# ChatBOT.net
KiCad netlist of a schematic drawn in EasyEDA Pro
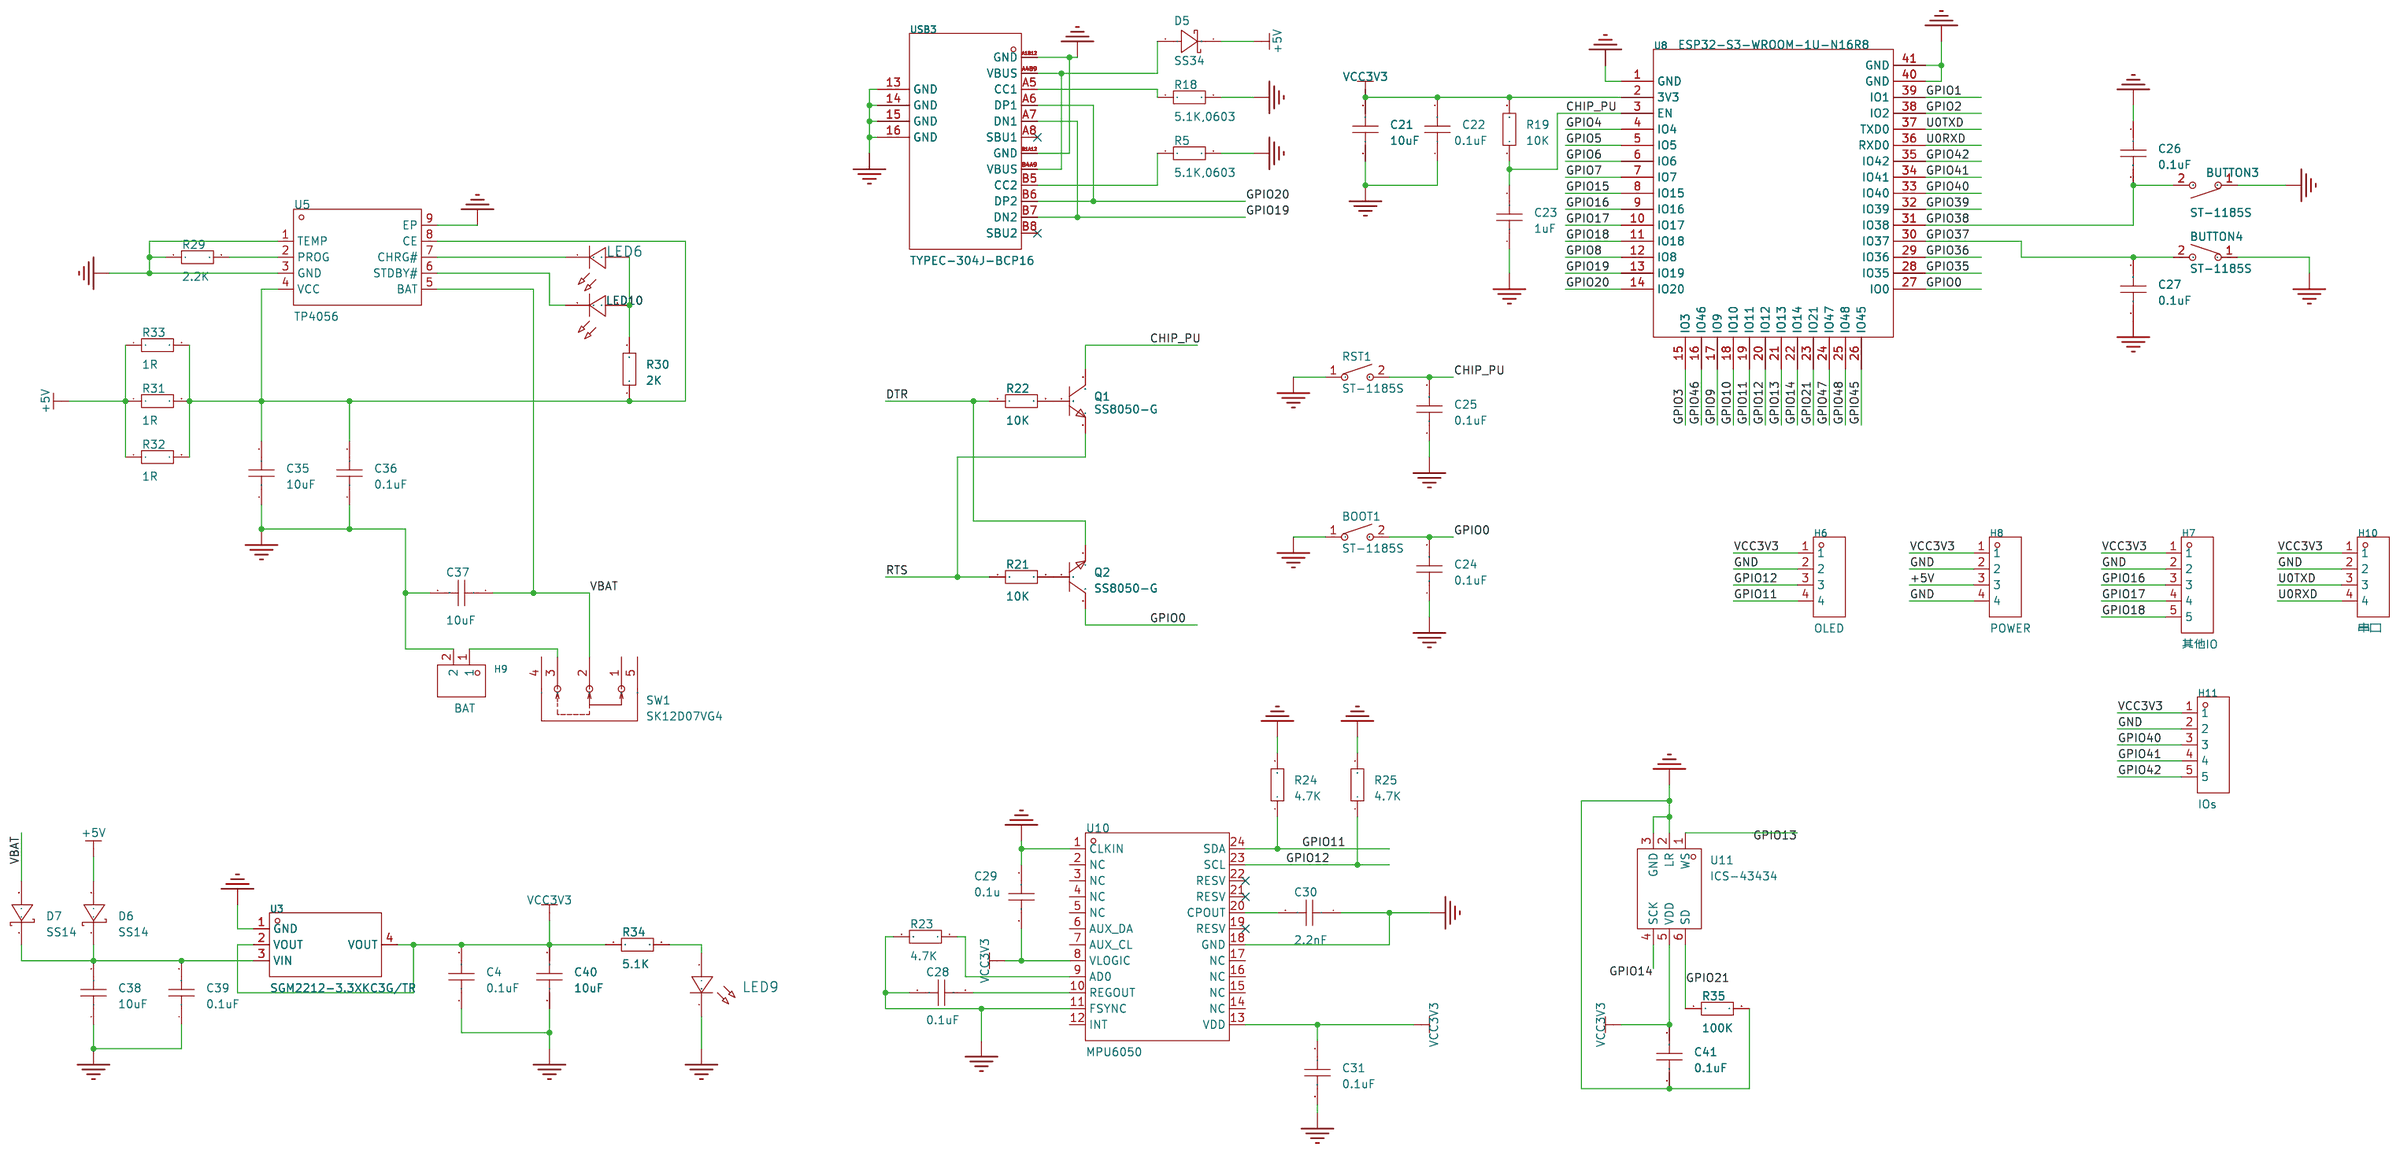
[diagram p0: schematic sheet]

(export (version "E")
  (design (tool "Eeschema 10.0.6"))
  (components
    (comp (ref "BOOT1")
      (value "ST-1185S")
      (footprint "easyedapro:SW-SMD_ST-1185S")
      (description "触点电流:50mA;额定电压(DC):12V;绝缘电阻:100MΩ;电路结构:单刀单掷;安装方式:立贴;机械寿命:10万次;带支架:否;")
      (fields (field (name "Manufacturer") "RISHENG(日昇)"))
      (libsource (lib "easyedapro") (part "ST-1185S"))
    )
    (comp (ref "BUTTON3")
      (value "ST-1185S")
      (footprint "easyedapro:SW-SMD_ST-1185S")
      (description "触点电流:50mA;额定电压(DC):12V;绝缘电阻:100MΩ;电路结构:单刀单掷;安装方式:立贴;机械寿命:10万次;带支架:否;")
      (fields (field (name "Manufacturer") "RISHENG(日昇)"))
      (libsource (lib "easyedapro") (part "ST-1185S"))
    )
    (comp (ref "BUTTON4")
      (value "ST-1185S")
      (footprint "easyedapro:SW-SMD_ST-1185S")
      (description "触点电流:50mA;额定电压(DC):12V;绝缘电阻:100MΩ;电路结构:单刀单掷;安装方式:立贴;机械寿命:10万次;带支架:否;")
      (fields (field (name "Manufacturer") "RISHENG(日昇)"))
      (libsource (lib "easyedapro") (part "ST-1185S"))
    )
    (comp (ref "C4")
      (value "0.1uF")
      (footprint "easyedapro:C0603")
      (libsource (lib "easyedapro") (part "CapAcitance"))
    )
    (comp (ref "C21")
      (value "10uF")
      (footprint "easyedapro:C0603")
      (libsource (lib "easyedapro") (part "CapAcitance"))
    )
    (comp (ref "C22")
      (value "0.1uF")
      (footprint "easyedapro:C0603")
      (libsource (lib "easyedapro") (part "CapAcitance"))
    )
    (comp (ref "C23")
      (value "1uF")
      (footprint "easyedapro:C0603")
      (libsource (lib "easyedapro") (part "CapAcitance"))
    )
    (comp (ref "C24")
      (value "0.1uF")
      (footprint "easyedapro:C0603")
      (libsource (lib "easyedapro") (part "CapAcitance"))
    )
    (comp (ref "C25")
      (value "0.1uF")
      (footprint "easyedapro:C0603")
      (libsource (lib "easyedapro") (part "CapAcitance"))
    )
    (comp (ref "C26")
      (value "0.1uF")
      (footprint "easyedapro:C0603")
      (libsource (lib "easyedapro") (part "CapAcitance"))
    )
    (comp (ref "C27")
      (value "0.1uF")
      (footprint "easyedapro:C0603")
      (libsource (lib "easyedapro") (part "CapAcitance"))
    )
    (comp (ref "C28")
      (value "0.1uF")
      (footprint "easyedapro:C0603")
      (libsource (lib "easyedapro") (part "CapAcitance"))
    )
    (comp (ref "C29")
      (value "0.1u")
      (footprint "easyedapro:C0603")
      (libsource (lib "easyedapro") (part "CapAcitance"))
    )
    (comp (ref "C30")
      (value "2.2nF")
      (footprint "easyedapro:C0603")
      (libsource (lib "easyedapro") (part "CapAcitance"))
    )
    (comp (ref "C31")
      (value "0.1uF")
      (footprint "easyedapro:C0603")
      (libsource (lib "easyedapro") (part "CapAcitance"))
    )
    (comp (ref "C35")
      (value "10uF")
      (footprint "easyedapro:C0603")
      (libsource (lib "easyedapro") (part "CapAcitance"))
    )
    (comp (ref "C36")
      (value "0.1uF")
      (footprint "easyedapro:C0603")
      (libsource (lib "easyedapro") (part "CapAcitance"))
    )
    (comp (ref "C37")
      (value "10uF")
      (footprint "easyedapro:C0603")
      (libsource (lib "easyedapro") (part "CapAcitance"))
    )
    (comp (ref "C38")
      (value "10uF")
      (footprint "easyedapro:C0603")
      (libsource (lib "easyedapro") (part "CapAcitance"))
    )
    (comp (ref "C39")
      (value "0.1uF")
      (footprint "easyedapro:C0603")
      (libsource (lib "easyedapro") (part "CapAcitance"))
    )
    (comp (ref "C40")
      (value "10uF")
      (footprint "easyedapro:C0603")
      (libsource (lib "easyedapro") (part "CapAcitance"))
    )
    (comp (ref "C41")
      (value "0.1uF")
      (footprint "easyedapro:C0603")
      (libsource (lib "easyedapro") (part "CapAcitance"))
    )
    (comp (ref "D5")
      (value "SS34")
      (footprint "easyedapro:SMA_L4.3-W2.5-LS5.0-RD")
      (description "二极管配置:独立式;直流反向耐压(Vr):40V;平均整流电流(Io):3A;正向压降(Vf):550mV@3A;")
      (fields (field (name "Manufacturer") "TWGMC(台湾迪嘉)"))
      (libsource (lib "easyedapro") (part "SS34_C727060"))
    )
    (comp (ref "D6")
      (value "SS14")
      (footprint "easyedapro:SMA_L4.2-W2.6-LS5.3-RD")
      (description "二极管配置:独立式;正向压降(Vf):550mV@1A;直流反向耐压(Vr):40V;平均整流电流(Io):1A;")
      (fields (field (name "Manufacturer") "MDD"))
      (libsource (lib "easyedapro") (part "SS14"))
    )
    (comp (ref "D7")
      (value "SS14")
      (footprint "easyedapro:SMA_L4.2-W2.6-LS5.3-RD")
      (description "二极管配置:独立式;正向压降(Vf):550mV@1A;直流反向耐压(Vr):40V;平均整流电流(Io):1A;")
      (fields (field (name "Manufacturer") "MDD"))
      (libsource (lib "easyedapro") (part "SS14"))
    )
    (comp (ref "H6")
      (value "OLED")
      (footprint "easyedapro:HDR-TH_4P-P2.54-V-M")
      (fields (field (name "Manufacturer") "XFCN(兴飞)"))
      (libsource (lib "easyedapro") (part "PZ254V-11-04P_C2691448"))
    )
    (comp (ref "H7")
      (value "其他IO")
      (footprint "easyedapro:HDR-TH_5P-P2.54-V-M")
      (fields (field (name "Manufacturer") "XFCN(兴飞)"))
      (libsource (lib "easyedapro") (part "PZ254V-11-05P"))
    )
    (comp (ref "H8")
      (value "POWER")
      (footprint "easyedapro:HDR-TH_4P-P2.54-V-M")
      (fields (field (name "Manufacturer") "XFCN(兴飞)"))
      (libsource (lib "easyedapro") (part "PZ254V-11-04P_C2691448"))
    )
    (comp (ref "H9")
      (value "BAT")
      (footprint "easyedapro:HDR-TH_2P-P2.54-V-M")
      (fields (field (name "Manufacturer") "XFCN(兴飞)"))
      (libsource (lib "easyedapro") (part "PZ254V-11-02P"))
    )
    (comp (ref "H10")
      (value "串口")
      (footprint "easyedapro:HDR-TH_4P-P2.54-V-M")
      (fields (field (name "Manufacturer") "XFCN(兴飞)"))
      (libsource (lib "easyedapro") (part "PZ254V-11-04P_C2691448"))
    )
    (comp (ref "H11")
      (value "IOs")
      (footprint "easyedapro:HDR-TH_5P-P2.54-V-M")
      (fields (field (name "Manufacturer") "XFCN(兴飞)"))
      (libsource (lib "easyedapro") (part "PZ254V-11-05P"))
    )
    (comp (ref "LED6")
      (value "~")
      (footprint "easyedapro:LED_0603")
      (libsource (lib "easyedapro") (part "LED_R"))
    )
    (comp (ref "LED9")
      (value "~")
      (footprint "easyedapro:LED_0603")
      (libsource (lib "easyedapro") (part "LED_R"))
    )
    (comp (ref "LED10")
      (value "~")
      (footprint "easyedapro:LED_0603")
      (libsource (lib "easyedapro") (part "LED_G"))
    )
    (comp (ref "Q1")
      (value "SS8050-G")
      (footprint "easyedapro:SOT-23-3_L2.9-W1.6-P1.90-LS2.8-BR")
      (description "晶体管类型:NPN;集射极击穿电压(Vceo):25V;集电极电流(Ic):1.5A;功率(Pd):300mW;直流电流增益(hFE@Ic,Vce):120@100mA,1V;")
      (fields (field (name "Manufacturer") "CJ(江苏长电/长晶)"))
      (libsource (lib "easyedapro") (part "SS8050-G"))
    )
    (comp (ref "Q2")
      (value "SS8050-G")
      (footprint "easyedapro:SOT-23-3_L2.9-W1.6-P1.90-LS2.8-BR")
      (description "晶体管类型:NPN;集射极击穿电压(Vceo):25V;集电极电流(Ic):1.5A;功率(Pd):300mW;直流电流增益(hFE@Ic,Vce):120@100mA,1V;")
      (fields (field (name "Manufacturer") "CJ(江苏长电/长晶)"))
      (libsource (lib "easyedapro") (part "SS8050-G"))
    )
    (comp (ref "R5")
      (value "5.1K,0603")
      (footprint "easyedapro:R0603")
      (libsource (lib "easyedapro") (part "电阻"))
    )
    (comp (ref "R18")
      (value "5.1K,0603")
      (footprint "easyedapro:R0603")
      (libsource (lib "easyedapro") (part "电阻"))
    )
    (comp (ref "R19") (value "10K") (footprint "easyedapro:R0603") (libsource (lib "easyedapro") (part "电阻")))
    (comp (ref "R21") (value "10K") (footprint "easyedapro:R0603") (libsource (lib "easyedapro") (part "电阻")))
    (comp (ref "R22") (value "10K") (footprint "easyedapro:R0603") (libsource (lib "easyedapro") (part "电阻")))
    (comp (ref "R23")
      (value "4.7K")
      (footprint "easyedapro:R0603")
      (libsource (lib "easyedapro") (part "电阻"))
    )
    (comp (ref "R24")
      (value "4.7K")
      (footprint "easyedapro:R0603")
      (libsource (lib "easyedapro") (part "电阻"))
    )
    (comp (ref "R25")
      (value "4.7K")
      (footprint "easyedapro:R0603")
      (libsource (lib "easyedapro") (part "电阻"))
    )
    (comp (ref "R29")
      (value "2.2K")
      (footprint "easyedapro:R0603")
      (libsource (lib "easyedapro") (part "电阻"))
    )
    (comp (ref "R30") (value "2K") (footprint "easyedapro:R0603") (libsource (lib "easyedapro") (part "电阻")))
    (comp (ref "R31") (value "1R") (footprint "easyedapro:R0603") (libsource (lib "easyedapro") (part "电阻")))
    (comp (ref "R32") (value "1R") (footprint "easyedapro:R0603") (libsource (lib "easyedapro") (part "电阻")))
    (comp (ref "R33") (value "1R") (footprint "easyedapro:R0603") (libsource (lib "easyedapro") (part "电阻")))
    (comp (ref "R34")
      (value "5.1K")
      (footprint "easyedapro:R0603")
      (libsource (lib "easyedapro") (part "电阻"))
    )
    (comp (ref "R35")
      (value "100K")
      (footprint "easyedapro:R0603")
      (libsource (lib "easyedapro") (part "电阻"))
    )
    (comp (ref "RST1")
      (value "ST-1185S")
      (footprint "easyedapro:SW-SMD_ST-1185S")
      (description "触点电流:50mA;额定电压(DC):12V;绝缘电阻:100MΩ;电路结构:单刀单掷;安装方式:立贴;机械寿命:10万次;带支架:否;")
      (fields (field (name "Manufacturer") "RISHENG(日昇)"))
      (libsource (lib "easyedapro") (part "ST-1185S"))
    )
    (comp (ref "SW1")
      (value "SK12D07VG4")
      (footprint "easyedapro:SW-TH_SK12D07VG4")
      (description "电路结构:单刀双掷;安装方式:卧插;额定电流(DC):500mA;额定电压(DC):50V;额定电流(AC):-;额定电压(AC):-;机械寿命:5千次;")
      (fields (field (name "Manufacturer") "SHOU HAN(首韩)"))
      (libsource (lib "easyedapro") (part "SK12D07VG4"))
    )
    (comp (ref "U3")
      (value "SGM2212-3.3XKC3G/TR")
      (footprint "easyedapro:SOT-223-3_L6.5-W3.4-P2.30-LS7.0-BR")
      (fields (field (name "Manufacturer") "SGMICRO(圣邦微)"))
      (libsource (lib "easyedapro") (part "SGM2212-3.3XKC3G/TR_C3294699"))
    )
    (comp (ref "U5")
      (value "TP4056")
      (footprint "easyedapro:ESOP-8_L4.9-W3.9-P1.27-LS6.0-BL-EP")
      (fields (field (name "Manufacturer") "UMW(友台半导体)"))
      (libsource (lib "easyedapro") (part "TP4056_C725790"))
    )
    (comp (ref "U8")
      (value "ESP32-S3-WROOM-1U-N16R8")
      (footprint "easyedapro:WIRELM-SMD_ESP32-S3-WROOM-1U")
      (fields (field (name "Manufacturer") "ESPRESSIF(乐鑫)"))
      (libsource (lib "easyedapro") (part "ESP32-S3-WROOM-1U-N16R8"))
    )
    (comp (ref "U10")
      (value "MPU6050")
      (footprint "easyedapro:QFN-24_L4.0-W4.0-P0.50-BL")
      (libsource (lib "easyedapro") (part "MPU6050_C9900042518"))
    )
    (comp (ref "U11")
      (value "ICS-43434")
      (footprint "easyedapro:MIC-SMD_6P-L3.5-W2.7-P0.90-TR")
      (description "方向:全指向;信噪比:64dB;灵敏度:-;")
      (fields (field (name "Manufacturer") "TDK InvenSense(应美盛)"))
      (libsource (lib "easyedapro") (part "ICS-43434_C5656610"))
    )
    (comp (ref "USB3")
      (value "TYPEC-304J-BCP16")
      (footprint "easyedapro:USB-C-SMD_TYPEC-304J-BCP16")
      (description "连接器类型:Type-C;标准:USB 3.1;公母:母座;触点数量:16;端口数量:1;安装方式:卧贴;额定电流 - 电源:5A;工作温度范围:-40℃~+85℃;焊接温度(最大值):260℃;")
      (fields (field (name "Manufacturer") "XUNPU(讯普)"))
      (libsource (lib "easyedapro") (part "TYPEC-304J-BCP16"))
    )
  )
  (nets
    (net (code "1") (name "+5V") (class "Default")
      (node (ref "D5") (pin "1") (pinfunction "C_1") (pintype "unspecified"))
      (node (ref "D6") (pin "2") (pinfunction "A_2") (pintype "unspecified"))
      (node (ref "H8") (pin "3") (pinfunction "3_3") (pintype "input"))
      (node (ref "R31") (pin "1") (pinfunction "1_1") (pintype "input"))
      (node (ref "R32") (pin "1") (pinfunction "1_1") (pintype "input"))
      (node (ref "R33") (pin "1") (pinfunction "1_1") (pintype "input"))
    )
    (net (code "2") (name "/CHIP_PU") (class "Default")
      (node (ref "C23") (pin "2") (pinfunction "2_2") (pintype "input"))
      (node (ref "C25") (pin "2") (pinfunction "2_2") (pintype "input"))
      (node (ref "Q1") (pin "3") (pinfunction "C_3") (pintype "input"))
      (node (ref "R19") (pin "1") (pinfunction "1_1") (pintype "input"))
      (node (ref "RST1") (pin "2") (pinfunction "2_2") (pintype "unspecified"))
      (node (ref "U8") (pin "3") (pinfunction "EN_3") (pintype "unspecified"))
    )
    (net (code "3") (name "/DTR") (class "Default")
      (node (ref "Q2") (pin "2") (pinfunction "E_2") (pintype "input"))
      (node (ref "R22") (pin "1") (pinfunction "1_1") (pintype "input"))
    )
    (net (code "4") (name "/GPIO0") (class "Default")
      (node (ref "BOOT1") (pin "2") (pinfunction "2_2") (pintype "unspecified"))
      (node (ref "C24") (pin "2") (pinfunction "2_2") (pintype "input"))
      (node (ref "Q2") (pin "3") (pinfunction "C_3") (pintype "input"))
      (node (ref "U8") (pin "27") (pinfunction "IO0_27") (pintype "unspecified"))
    )
    (net (code "5") (name "/GPIO1") (class "Default")
      (node (ref "U8") (pin "39") (pinfunction "IO1_39") (pintype "unspecified"))
    )
    (net (code "6") (name "/GPIO2") (class "Default")
      (node (ref "U8") (pin "38") (pinfunction "IO2_38") (pintype "unspecified"))
    )
    (net (code "7") (name "/GPIO3") (class "Default")
      (node (ref "U8") (pin "15") (pinfunction "IO3_15") (pintype "unspecified"))
    )
    (net (code "8") (name "/GPIO4") (class "Default")
      (node (ref "U8") (pin "4") (pinfunction "IO4_4") (pintype "unspecified"))
    )
    (net (code "9") (name "/GPIO5") (class "Default")
      (node (ref "U8") (pin "5") (pinfunction "IO5_5") (pintype "unspecified"))
    )
    (net (code "10") (name "/GPIO6") (class "Default")
      (node (ref "U8") (pin "6") (pinfunction "IO6_6") (pintype "unspecified"))
    )
    (net (code "11") (name "/GPIO7") (class "Default")
      (node (ref "U8") (pin "7") (pinfunction "IO7_7") (pintype "unspecified"))
    )
    (net (code "12") (name "/GPIO8") (class "Default")
      (node (ref "U8") (pin "12") (pinfunction "IO8_12") (pintype "unspecified"))
    )
    (net (code "13") (name "/GPIO9") (class "Default")
      (node (ref "U8") (pin "17") (pinfunction "IO9_17") (pintype "unspecified"))
    )
    (net (code "14") (name "/GPIO10") (class "Default")
      (node (ref "U8") (pin "18") (pinfunction "IO10_18") (pintype "unspecified"))
    )
    (net (code "15") (name "/GPIO11") (class "Default")
      (node (ref "H6") (pin "4") (pinfunction "4_4") (pintype "input"))
      (node (ref "R24") (pin "1") (pinfunction "1_1") (pintype "input"))
      (node (ref "U10") (pin "24") (pinfunction "SDA_24") (pintype "unspecified"))
      (node (ref "U8") (pin "19") (pinfunction "IO11_19") (pintype "unspecified"))
    )
    (net (code "16") (name "/GPIO12") (class "Default")
      (node (ref "H6") (pin "3") (pinfunction "3_3") (pintype "input"))
      (node (ref "R25") (pin "1") (pinfunction "1_1") (pintype "input"))
      (node (ref "U10") (pin "23") (pinfunction "SCL_23") (pintype "unspecified"))
      (node (ref "U8") (pin "20") (pinfunction "IO12_20") (pintype "unspecified"))
    )
    (net (code "17") (name "/GPIO13") (class "Default")
      (node (ref "U11") (pin "1") (pinfunction "WS_1") (pintype "unspecified"))
      (node (ref "U8") (pin "21") (pinfunction "IO13_21") (pintype "unspecified"))
    )
    (net (code "18") (name "/GPIO14") (class "Default")
      (node (ref "U11") (pin "4") (pinfunction "SCK_4") (pintype "unspecified"))
      (node (ref "U8") (pin "22") (pinfunction "IO14_22") (pintype "unspecified"))
    )
    (net (code "19") (name "/GPIO15") (class "Default")
      (node (ref "U8") (pin "8") (pinfunction "IO15_8") (pintype "unspecified"))
    )
    (net (code "20") (name "/GPIO16") (class "Default")
      (node (ref "H7") (pin "3") (pinfunction "3_3") (pintype "unspecified"))
      (node (ref "U8") (pin "9") (pinfunction "IO16_9") (pintype "unspecified"))
    )
    (net (code "21") (name "/GPIO17") (class "Default")
      (node (ref "H7") (pin "4") (pinfunction "4_4") (pintype "unspecified"))
      (node (ref "U8") (pin "10") (pinfunction "IO17_10") (pintype "unspecified"))
    )
    (net (code "22") (name "/GPIO18") (class "Default")
      (node (ref "H7") (pin "5") (pinfunction "5_5") (pintype "unspecified"))
      (node (ref "U8") (pin "11") (pinfunction "IO18_11") (pintype "unspecified"))
    )
    (net (code "23") (name "/GPIO19") (class "Default")
      (node (ref "U8") (pin "13") (pinfunction "IO19_13") (pintype "unspecified"))
      (node (ref "USB3") (pin "A7") (pinfunction "DN1_A7") (pintype "unspecified"))
      (node (ref "USB3") (pin "B7") (pinfunction "DN2_B7") (pintype "unspecified"))
    )
    (net (code "24") (name "/GPIO20") (class "Default")
      (node (ref "U8") (pin "14") (pinfunction "IO20_14") (pintype "unspecified"))
      (node (ref "USB3") (pin "A6") (pinfunction "DP1_A6") (pintype "unspecified"))
      (node (ref "USB3") (pin "B6") (pinfunction "DP2_B6") (pintype "unspecified"))
    )
    (net (code "25") (name "/GPIO21") (class "Default")
      (node (ref "R35") (pin "1") (pinfunction "1_1") (pintype "input"))
      (node (ref "U11") (pin "6") (pinfunction "SD_6") (pintype "unspecified"))
      (node (ref "U8") (pin "23") (pinfunction "IO21_23") (pintype "unspecified"))
    )
    (net (code "26") (name "/GPIO35") (class "Default")
      (node (ref "U8") (pin "28") (pinfunction "IO35_28") (pintype "unspecified"))
    )
    (net (code "27") (name "/GPIO36") (class "Default")
      (node (ref "U8") (pin "29") (pinfunction "IO36_29") (pintype "unspecified"))
    )
    (net (code "28") (name "/GPIO37") (class "Default")
      (node (ref "BUTTON4") (pin "2") (pinfunction "2_2") (pintype "unspecified"))
      (node (ref "C27") (pin "2") (pinfunction "2_2") (pintype "input"))
      (node (ref "U8") (pin "30") (pinfunction "IO37_30") (pintype "unspecified"))
    )
    (net (code "29") (name "/GPIO38") (class "Default")
      (node (ref "BUTTON3") (pin "2") (pinfunction "2_2") (pintype "unspecified"))
      (node (ref "C26") (pin "2") (pinfunction "2_2") (pintype "input"))
      (node (ref "U8") (pin "31") (pinfunction "IO38_31") (pintype "unspecified"))
    )
    (net (code "30") (name "/GPIO39") (class "Default")
      (node (ref "U8") (pin "32") (pinfunction "IO39_32") (pintype "unspecified"))
    )
    (net (code "31") (name "/GPIO40") (class "Default")
      (node (ref "H11") (pin "3") (pinfunction "3_3") (pintype "unspecified"))
      (node (ref "U8") (pin "33") (pinfunction "IO40_33") (pintype "unspecified"))
    )
    (net (code "32") (name "/GPIO41") (class "Default")
      (node (ref "H11") (pin "4") (pinfunction "4_4") (pintype "unspecified"))
      (node (ref "U8") (pin "34") (pinfunction "IO41_34") (pintype "unspecified"))
    )
    (net (code "33") (name "/GPIO42") (class "Default")
      (node (ref "H11") (pin "5") (pinfunction "5_5") (pintype "unspecified"))
      (node (ref "U8") (pin "35") (pinfunction "IO42_35") (pintype "unspecified"))
    )
    (net (code "34") (name "/GPIO45") (class "Default")
      (node (ref "U8") (pin "26") (pinfunction "IO45_26") (pintype "unspecified"))
    )
    (net (code "35") (name "/GPIO46") (class "Default")
      (node (ref "U8") (pin "16") (pinfunction "IO46_16") (pintype "unspecified"))
    )
    (net (code "36") (name "/GPIO47") (class "Default")
      (node (ref "U8") (pin "24") (pinfunction "IO47_24") (pintype "unspecified"))
    )
    (net (code "37") (name "/GPIO48") (class "Default")
      (node (ref "U8") (pin "25") (pinfunction "IO48_25") (pintype "unspecified"))
    )
    (net (code "38") (name "/RTS") (class "Default")
      (node (ref "Q1") (pin "2") (pinfunction "E_2") (pintype "input"))
      (node (ref "R21") (pin "1") (pinfunction "1_1") (pintype "input"))
    )
    (net (code "39") (name "/U0RXD") (class "Default")
      (node (ref "H10") (pin "4") (pinfunction "4_4") (pintype "input"))
      (node (ref "U8") (pin "36") (pinfunction "RXD0_36") (pintype "unspecified"))
    )
    (net (code "40") (name "/U0TXD") (class "Default")
      (node (ref "H10") (pin "3") (pinfunction "3_3") (pintype "input"))
      (node (ref "U8") (pin "37") (pinfunction "TXD0_37") (pintype "unspecified"))
    )
    (net (code "41") (name "/VBAT") (class "Default")
      (node (ref "C37") (pin "1") (pinfunction "1_1") (pintype "input"))
      (node (ref "D7") (pin "2") (pinfunction "A_2") (pintype "unspecified"))
      (node (ref "SW1") (pin "2") (pinfunction "2_2") (pintype "unspecified"))
      (node (ref "U5") (pin "5") (pinfunction "BAT_5") (pintype "unspecified"))
    )
    (net (code "42") (name "GND") (class "Default")
      (node (ref "BOOT1") (pin "1") (pinfunction "1_1") (pintype "unspecified"))
      (node (ref "BUTTON3") (pin "1") (pinfunction "1_1") (pintype "unspecified"))
      (node (ref "BUTTON4") (pin "1") (pinfunction "1_1") (pintype "unspecified"))
      (node (ref "C21") (pin "1") (pinfunction "1_1") (pintype "input"))
      (node (ref "C22") (pin "1") (pinfunction "1_1") (pintype "input"))
      (node (ref "C23") (pin "1") (pinfunction "1_1") (pintype "input"))
      (node (ref "C24") (pin "1") (pinfunction "1_1") (pintype "input"))
      (node (ref "C25") (pin "1") (pinfunction "1_1") (pintype "input"))
      (node (ref "C26") (pin "1") (pinfunction "1_1") (pintype "input"))
      (node (ref "C27") (pin "1") (pinfunction "1_1") (pintype "input"))
      (node (ref "C28") (pin "1") (pinfunction "1_1") (pintype "input"))
      (node (ref "C29") (pin "1") (pinfunction "1_1") (pintype "input"))
      (node (ref "C30") (pin "1") (pinfunction "1_1") (pintype "input"))
      (node (ref "C31") (pin "2") (pinfunction "2_2") (pintype "input"))
      (node (ref "C35") (pin "1") (pinfunction "1_1") (pintype "input"))
      (node (ref "C36") (pin "1") (pinfunction "1_1") (pintype "input"))
      (node (ref "C37") (pin "2") (pinfunction "2_2") (pintype "input"))
      (node (ref "C38") (pin "1") (pinfunction "1_1") (pintype "input"))
      (node (ref "C39") (pin "1") (pinfunction "1_1") (pintype "input"))
      (node (ref "C4") (pin "1") (pinfunction "1_1") (pintype "input"))
      (node (ref "C40") (pin "1") (pinfunction "1_1") (pintype "input"))
      (node (ref "C41") (pin "1") (pinfunction "1_1") (pintype "input"))
      (node (ref "H10") (pin "2") (pinfunction "2_2") (pintype "input"))
      (node (ref "H11") (pin "2") (pinfunction "2_2") (pintype "unspecified"))
      (node (ref "H6") (pin "2") (pinfunction "2_2") (pintype "input"))
      (node (ref "H7") (pin "2") (pinfunction "2_2") (pintype "unspecified"))
      (node (ref "H8") (pin "2") (pinfunction "2_2") (pintype "input"))
      (node (ref "H8") (pin "4") (pinfunction "4_4") (pintype "input"))
      (node (ref "H9") (pin "2") (pinfunction "2_2") (pintype "input"))
      (node (ref "LED9") (pin "1") (pinfunction "C_1") (pintype "input"))
      (node (ref "R18") (pin "2") (pinfunction "2_2") (pintype "input"))
      (node (ref "R23") (pin "2") (pinfunction "2_2") (pintype "input"))
      (node (ref "R24") (pin "2") (pinfunction "2_2") (pintype "input"))
      (node (ref "R25") (pin "2") (pinfunction "2_2") (pintype "input"))
      (node (ref "R29") (pin "1") (pinfunction "1_1") (pintype "input"))
      (node (ref "R35") (pin "2") (pinfunction "2_2") (pintype "input"))
      (node (ref "R5") (pin "2") (pinfunction "2_2") (pintype "input"))
      (node (ref "RST1") (pin "1") (pinfunction "1_1") (pintype "unspecified"))
      (node (ref "U10") (pin "1") (pinfunction "CLKIN_1") (pintype "unspecified"))
      (node (ref "U10") (pin "11") (pinfunction "FSYNC_11") (pintype "unspecified"))
      (node (ref "U10") (pin "18") (pinfunction "GND_18") (pintype "unspecified"))
      (node (ref "U11") (pin "2") (pinfunction "LR_2") (pintype "unspecified"))
      (node (ref "U11") (pin "3") (pinfunction "GND_3") (pintype "unspecified"))
      (node (ref "U3") (pin "1") (pinfunction "GND_1") (pintype "unspecified"))
      (node (ref "U5") (pin "1") (pinfunction "TEMP_1") (pintype "unspecified"))
      (node (ref "U5") (pin "3") (pinfunction "GND_3") (pintype "unspecified"))
      (node (ref "U5") (pin "9") (pinfunction "EP_9") (pintype "unspecified"))
      (node (ref "U8") (pin "1") (pinfunction "GND_1") (pintype "unspecified"))
      (node (ref "U8") (pin "40") (pinfunction "GND_40") (pintype "unspecified"))
      (node (ref "U8") (pin "41") (pinfunction "GND_41") (pintype "unspecified"))
      (node (ref "USB3") (pin "13") (pinfunction "GND_13") (pintype "unspecified"))
      (node (ref "USB3") (pin "14") (pinfunction "GND_14") (pintype "unspecified"))
      (node (ref "USB3") (pin "15") (pinfunction "GND_15") (pintype "unspecified"))
      (node (ref "USB3") (pin "16") (pinfunction "GND_16") (pintype "unspecified"))
      (node (ref "USB3") (pin "A1B12") (pinfunction "GND_A1B12") (pintype "unspecified"))
      (node (ref "USB3") (pin "B1A12") (pinfunction "GND_B1A12") (pintype "unspecified"))
    )
    (net (code "43") (name "Net-(D5-A)") (class "Default")
      (node (ref "D5") (pin "2") (pinfunction "A_2") (pintype "unspecified"))
      (node (ref "USB3") (pin "A4B9") (pinfunction "VBUS_A4B9") (pintype "unspecified"))
      (node (ref "USB3") (pin "B4A9") (pinfunction "VBUS_B4A9") (pintype "unspecified"))
    )
    (net (code "44") (name "Net-(D6-K)") (class "Default")
      (node (ref "C38") (pin "2") (pinfunction "2_2") (pintype "input"))
      (node (ref "C39") (pin "2") (pinfunction "2_2") (pintype "input"))
      (node (ref "D6") (pin "1") (pinfunction "K_1") (pintype "unspecified"))
      (node (ref "D7") (pin "1") (pinfunction "K_1") (pintype "unspecified"))
      (node (ref "U3") (pin "3") (pinfunction "VIN_3") (pintype "unspecified"))
    )
    (net (code "45") (name "Net-(H9-Pad1)") (class "Default")
      (node (ref "H9") (pin "1") (pinfunction "1_1") (pintype "input"))
      (node (ref "SW1") (pin "3") (pinfunction "3_3") (pintype "unspecified"))
    )
    (net (code "46") (name "Net-(LED6-C)") (class "Default")
      (node (ref "LED6") (pin "1") (pinfunction "C_1") (pintype "input"))
      (node (ref "U5") (pin "7") (pinfunction "CHRG#_7") (pintype "unspecified"))
    )
    (net (code "47") (name "Net-(LED9-A)") (class "Default")
      (node (ref "LED9") (pin "2") (pinfunction "A_2") (pintype "input"))
      (node (ref "R34") (pin "2") (pinfunction "2_2") (pintype "input"))
    )
    (net (code "48") (name "Net-(LED10-A)") (class "Default")
      (node (ref "LED10") (pin "2") (pinfunction "A_2") (pintype "input"))
      (node (ref "LED6") (pin "2") (pinfunction "A_2") (pintype "input"))
      (node (ref "R30") (pin "2") (pinfunction "2_2") (pintype "input"))
    )
    (net (code "49") (name "Net-(LED10-C)") (class "Default")
      (node (ref "LED10") (pin "1") (pinfunction "C_1") (pintype "input"))
      (node (ref "U5") (pin "6") (pinfunction "STDBY#_6") (pintype "unspecified"))
    )
    (net (code "50") (name "Net-(Q1-B)") (class "Default")
      (node (ref "Q1") (pin "1") (pinfunction "B_1") (pintype "input"))
      (node (ref "R22") (pin "2") (pinfunction "2_2") (pintype "input"))
    )
    (net (code "51") (name "Net-(Q2-B)") (class "Default")
      (node (ref "Q2") (pin "1") (pinfunction "B_1") (pintype "input"))
      (node (ref "R21") (pin "2") (pinfunction "2_2") (pintype "input"))
    )
    (net (code "52") (name "Net-(U5-CE)") (class "Default")
      (node (ref "C35") (pin "2") (pinfunction "2_2") (pintype "input"))
      (node (ref "C36") (pin "2") (pinfunction "2_2") (pintype "input"))
      (node (ref "R30") (pin "1") (pinfunction "1_1") (pintype "input"))
      (node (ref "R31") (pin "2") (pinfunction "2_2") (pintype "input"))
      (node (ref "R32") (pin "2") (pinfunction "2_2") (pintype "input"))
      (node (ref "R33") (pin "2") (pinfunction "2_2") (pintype "input"))
      (node (ref "U5") (pin "4") (pinfunction "VCC_4") (pintype "unspecified"))
      (node (ref "U5") (pin "8") (pinfunction "CE_8") (pintype "unspecified"))
    )
    (net (code "53") (name "Net-(U5-PROG)") (class "Default")
      (node (ref "R29") (pin "2") (pinfunction "2_2") (pintype "input"))
      (node (ref "U5") (pin "2") (pinfunction "PROG_2") (pintype "unspecified"))
    )
    (net (code "54") (name "Net-(U10-AD0)") (class "Default")
      (node (ref "R23") (pin "1") (pinfunction "1_1") (pintype "input"))
      (node (ref "U10") (pin "9") (pinfunction "AD0_9") (pintype "unspecified"))
    )
    (net (code "55") (name "Net-(U10-CPOUT)") (class "Default")
      (node (ref "C30") (pin "2") (pinfunction "2_2") (pintype "input"))
      (node (ref "U10") (pin "20") (pinfunction "CPOUT_20") (pintype "unspecified"))
    )
    (net (code "56") (name "Net-(U10-REGOUT)") (class "Default")
      (node (ref "C28") (pin "2") (pinfunction "2_2") (pintype "input"))
      (node (ref "U10") (pin "10") (pinfunction "REGOUT_10") (pintype "unspecified"))
    )
    (net (code "57") (name "Net-(USB3-CC1)") (class "Default")
      (node (ref "R18") (pin "1") (pinfunction "1_1") (pintype "input"))
      (node (ref "USB3") (pin "A5") (pinfunction "CC1_A5") (pintype "unspecified"))
    )
    (net (code "58") (name "Net-(USB3-CC2)") (class "Default")
      (node (ref "R5") (pin "1") (pinfunction "1_1") (pintype "input"))
      (node (ref "USB3") (pin "B5") (pinfunction "CC2_B5") (pintype "unspecified"))
    )
    (net (code "59") (name "VCC3V3") (class "Default")
      (node (ref "C21") (pin "2") (pinfunction "2_2") (pintype "input"))
      (node (ref "C22") (pin "2") (pinfunction "2_2") (pintype "input"))
      (node (ref "C29") (pin "2") (pinfunction "2_2") (pintype "input"))
      (node (ref "C31") (pin "1") (pinfunction "1_1") (pintype "input"))
      (node (ref "C4") (pin "2") (pinfunction "2_2") (pintype "input"))
      (node (ref "C40") (pin "2") (pinfunction "2_2") (pintype "input"))
      (node (ref "C41") (pin "2") (pinfunction "2_2") (pintype "input"))
      (node (ref "H10") (pin "1") (pinfunction "1_1") (pintype "input"))
      (node (ref "H11") (pin "1") (pinfunction "1_1") (pintype "unspecified"))
      (node (ref "H6") (pin "1") (pinfunction "1_1") (pintype "input"))
      (node (ref "H7") (pin "1") (pinfunction "1_1") (pintype "unspecified"))
      (node (ref "H8") (pin "1") (pinfunction "1_1") (pintype "input"))
      (node (ref "R19") (pin "2") (pinfunction "2_2") (pintype "input"))
      (node (ref "R34") (pin "1") (pinfunction "1_1") (pintype "input"))
      (node (ref "U10") (pin "13") (pinfunction "VDD_13") (pintype "unspecified"))
      (node (ref "U10") (pin "8") (pinfunction "VLOGIC_8") (pintype "unspecified"))
      (node (ref "U11") (pin "5") (pinfunction "VDD_5") (pintype "unspecified"))
      (node (ref "U3") (pin "2") (pinfunction "VOUT_2") (pintype "unspecified"))
      (node (ref "U3") (pin "4") (pinfunction "VOUT_4") (pintype "unspecified"))
      (node (ref "U8") (pin "2") (pinfunction "3V3_2") (pintype "unspecified"))
    )
    (net (code "60") (name "unconnected-(SW1-Pad1)") (class "Default")
      (node (ref "SW1") (pin "1") (pinfunction "1_1") (pintype "unspecified"))
    )
    (net (code "61") (name "unconnected-(SW1-Pad4)") (class "Default")
      (node (ref "SW1") (pin "4") (pinfunction "4_4") (pintype "unspecified"))
    )
    (net (code "62") (name "unconnected-(SW1-Pad5)") (class "Default")
      (node (ref "SW1") (pin "5") (pinfunction "5_5") (pintype "unspecified"))
    )
    (net (code "63") (name "unconnected-(U10-AUX_CL-Pad7)") (class "Default")
      (node (ref "U10") (pin "7") (pinfunction "AUX_CL_7") (pintype "unspecified"))
    )
    (net (code "64") (name "unconnected-(U10-AUX_DA-Pad6)") (class "Default")
      (node (ref "U10") (pin "6") (pinfunction "AUX_DA_6") (pintype "unspecified"))
    )
    (net (code "65") (name "unconnected-(U10-INT-Pad12)") (class "Default")
      (node (ref "U10") (pin "12") (pinfunction "INT_12") (pintype "unspecified"))
    )
    (net (code "66") (name "unconnected-(U10-NC-Pad2)") (class "Default")
      (node (ref "U10") (pin "2") (pinfunction "NC_2") (pintype "unspecified"))
    )
    (net (code "67") (name "unconnected-(U10-NC-Pad3)") (class "Default")
      (node (ref "U10") (pin "3") (pinfunction "NC_3") (pintype "unspecified"))
    )
    (net (code "68") (name "unconnected-(U10-NC-Pad4)") (class "Default")
      (node (ref "U10") (pin "4") (pinfunction "NC_4") (pintype "unspecified"))
    )
    (net (code "69") (name "unconnected-(U10-NC-Pad5)") (class "Default")
      (node (ref "U10") (pin "5") (pinfunction "NC_5") (pintype "unspecified"))
    )
    (net (code "70") (name "unconnected-(U10-NC-Pad14)") (class "Default")
      (node (ref "U10") (pin "14") (pinfunction "NC_14") (pintype "unspecified"))
    )
    (net (code "71") (name "unconnected-(U10-NC-Pad15)") (class "Default")
      (node (ref "U10") (pin "15") (pinfunction "NC_15") (pintype "unspecified"))
    )
    (net (code "72") (name "unconnected-(U10-NC-Pad16)") (class "Default")
      (node (ref "U10") (pin "16") (pinfunction "NC_16") (pintype "unspecified"))
    )
    (net (code "73") (name "unconnected-(U10-NC-Pad17)") (class "Default")
      (node (ref "U10") (pin "17") (pinfunction "NC_17") (pintype "unspecified"))
    )
    (net (code "74") (name "unconnected-(U10-RESV-Pad19)") (class "Default")
      (node (ref "U10") (pin "19") (pinfunction "RESV_19") (pintype "unspecified+no_connect"))
    )
    (net (code "75") (name "unconnected-(U10-RESV-Pad21)") (class "Default")
      (node (ref "U10") (pin "21") (pinfunction "RESV_21") (pintype "unspecified+no_connect"))
    )
    (net (code "76") (name "unconnected-(U10-RESV-Pad22)") (class "Default")
      (node (ref "U10") (pin "22") (pinfunction "RESV_22") (pintype "unspecified+no_connect"))
    )
    (net (code "77") (name "unconnected-(USB3-SBU1-PadA8)") (class "Default")
      (node (ref "USB3") (pin "A8") (pinfunction "SBU1_A8") (pintype "unspecified+no_connect"))
    )
    (net (code "78") (name "unconnected-(USB3-SBU2-PadB8)") (class "Default")
      (node (ref "USB3") (pin "B8") (pinfunction "SBU2_B8") (pintype "unspecified+no_connect"))
    )
  )
)
